# H-BRIDGE.net
KiCad netlist of a schematic drawn in Altium Designer
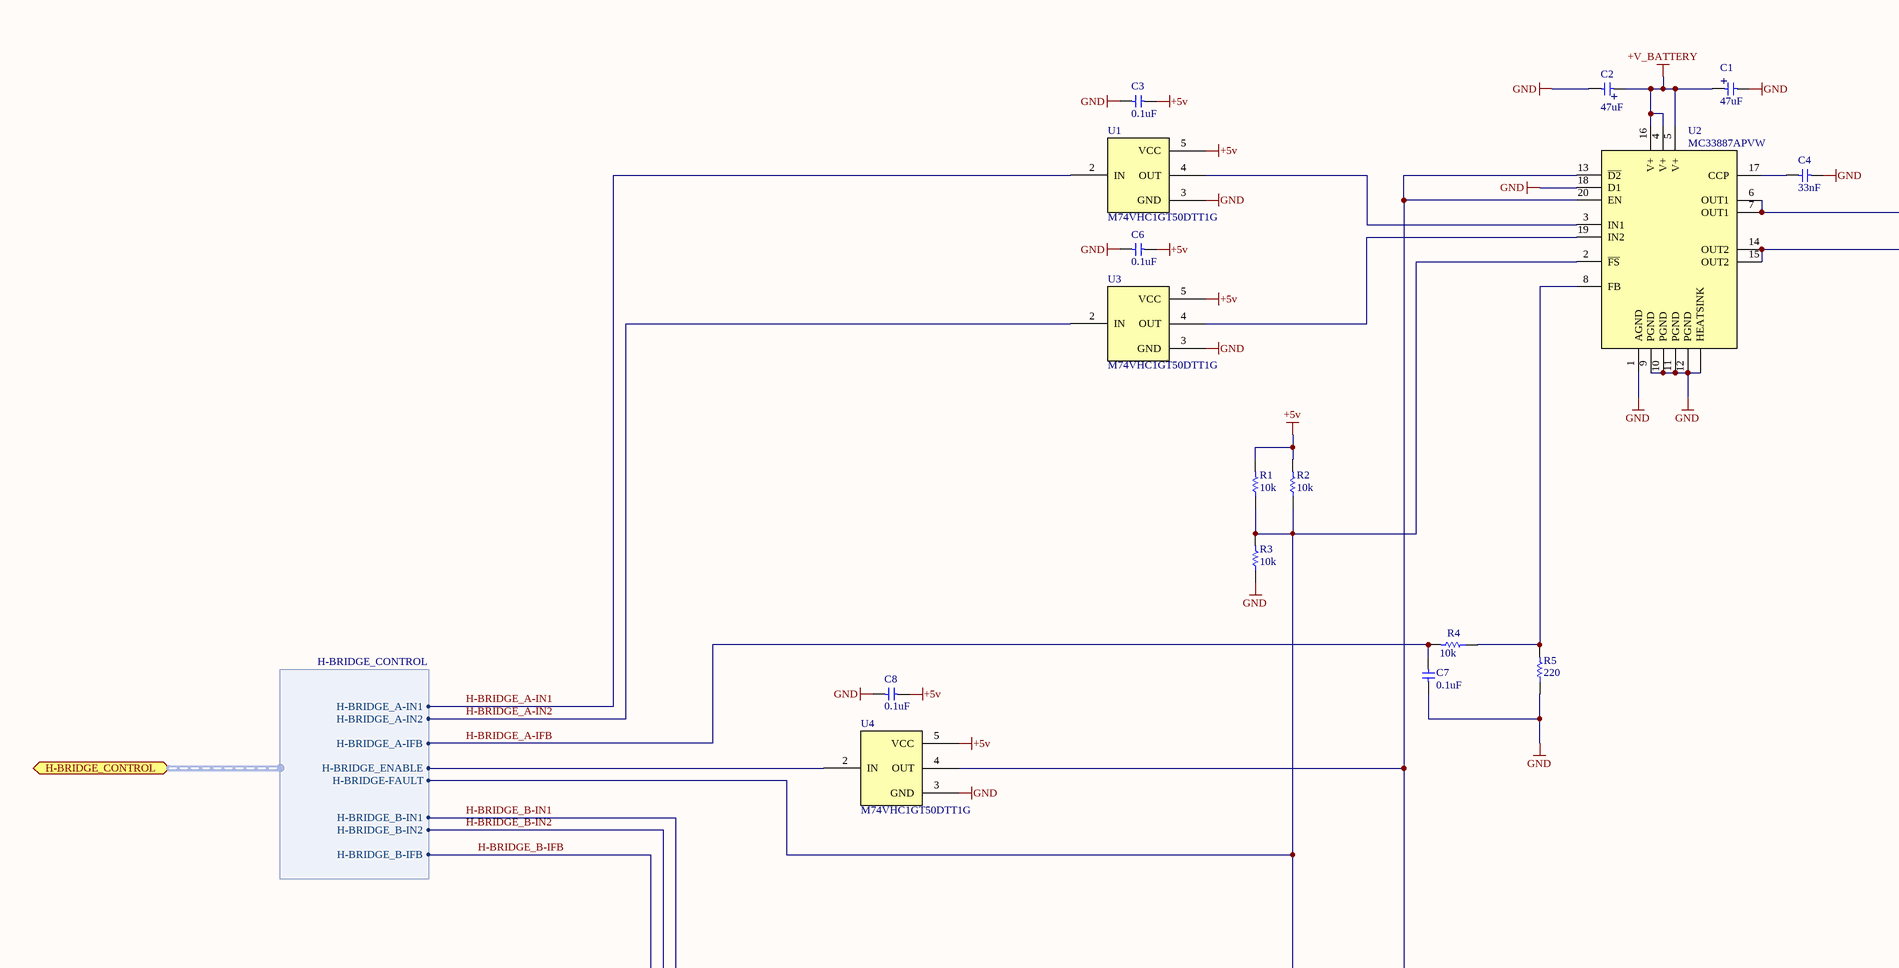
[diagram p0: H-BRIDGE.SchDoc, top left]
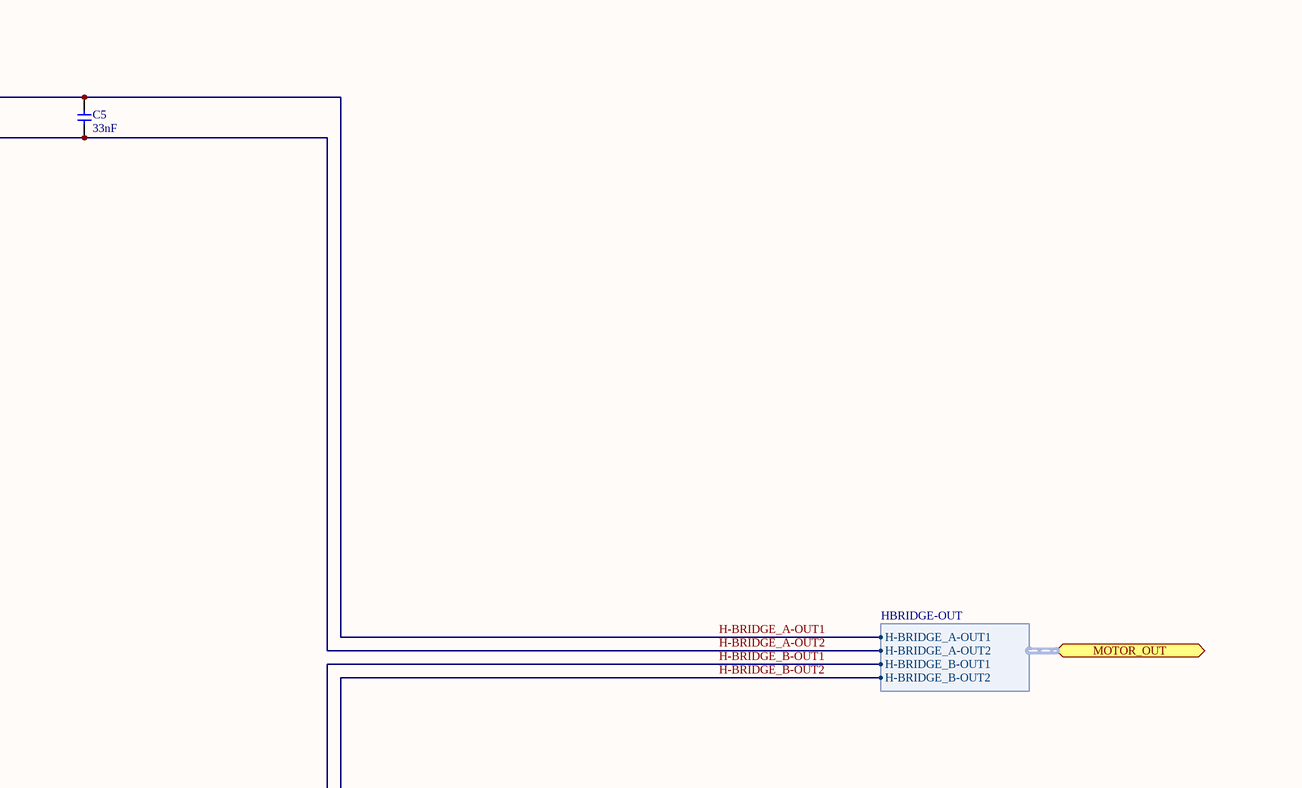
[diagram p1: H-BRIDGE.SchDoc, top right]
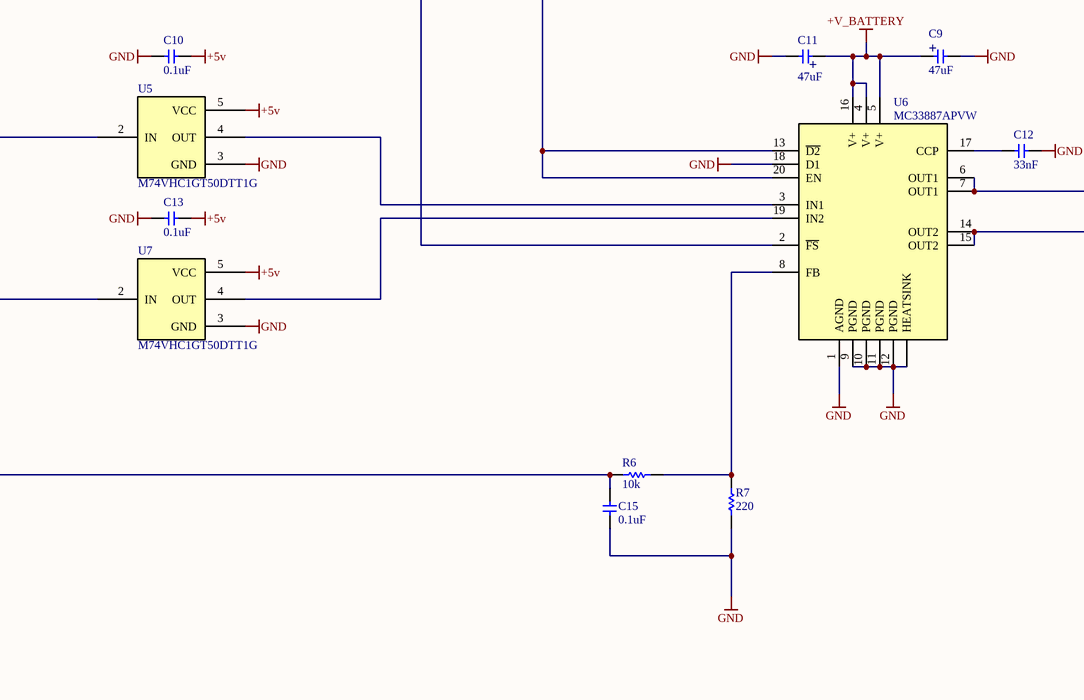
[diagram p2: H-BRIDGE.SchDoc, bottom left]
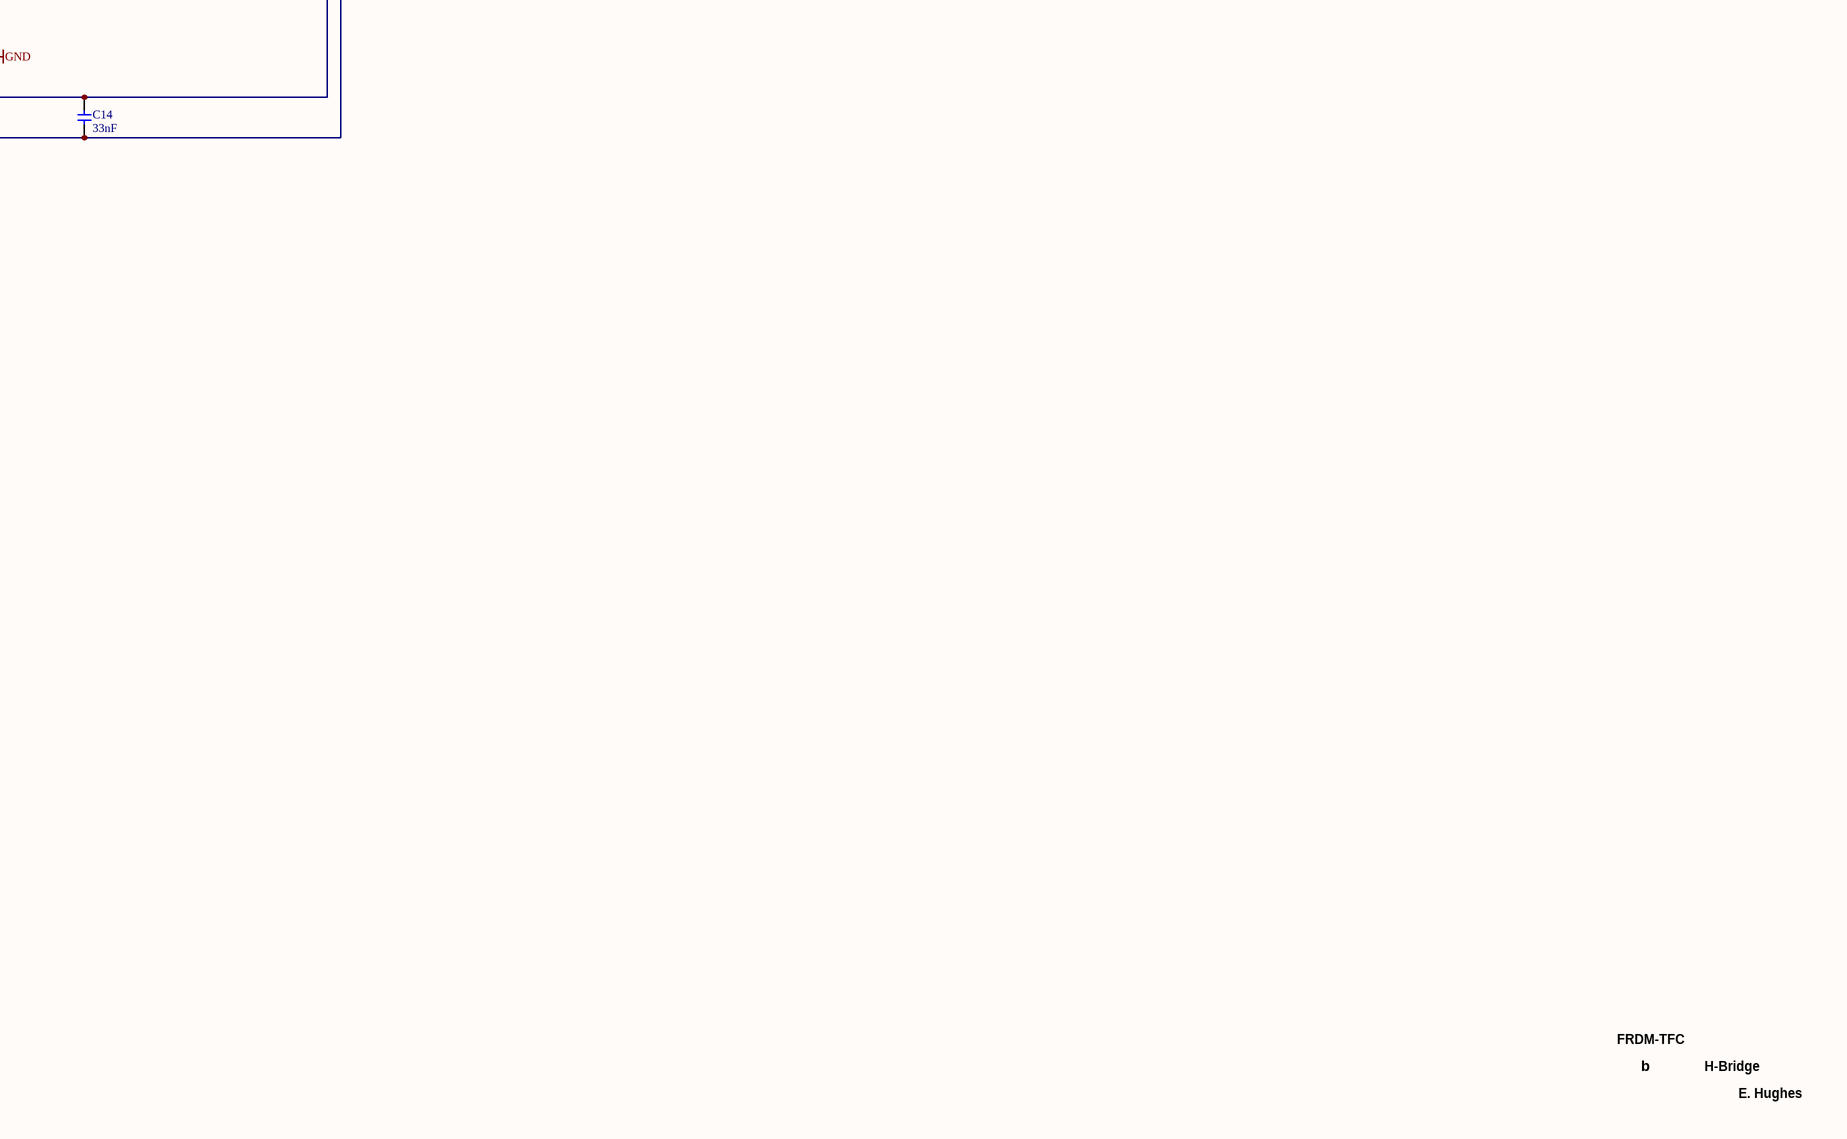
[diagram p3: H-BRIDGE.SchDoc, bottom right]

(export (version "E")
  (design (tool "Eeschema 10.0.6"))
  (components
    (comp (ref "C1")
      (value "47uF")
      (footprint "PANASONIC_D")
      (description "CAP ELECT 47UF 25V VS SMD")
      (fields
        (field (name "MANUFACTURER") "Panasonic - ECG")
        (field (name "MANUFACTURER PART NUMBER") "EEE-1EA470WP")
      )
      (libsource (lib "eCapacitors") (part "EEE-1EA470WP"))
    )
    (comp (ref "C2")
      (value "47uF")
      (footprint "PANASONIC_D")
      (description "CAP ELECT 47UF 25V VS SMD")
      (fields
        (field (name "MANUFACTURER") "Panasonic - ECG")
        (field (name "MANUFACTURER PART NUMBER") "EEE-1EA470WP")
      )
      (libsource (lib "eCapacitors") (part "EEE-1EA470WP"))
    )
    (comp (ref "C3")
      (value "0.1uF")
      (footprint "C0603")
      (description "CAP CER .1UF 50V 10% X7R 0603")
      (fields
        (field (name "MANUFACTURER") "Murata Electronics North America")
        (field (name "MANUFACTURER PART NUMBER") "GRM188R71H104KA93D")
      )
      (libsource (lib "eCapacitors") (part "GRM188R71H104KA93D"))
    )
    (comp (ref "C4")
      (value "33nF")
      (footprint "C0603")
      (description "CAP CER 0.033UF 50V 10% X7R 0603")
      (fields
        (field (name "MANUFACTURER") "Murata Electronics North America")
        (field (name "MANUFACTURER PART NUMBER") "GRM188R71H333KA61D")
      )
      (libsource (lib "eCapacitors") (part "GRM188R71H333KA61D"))
    )
    (comp (ref "C5")
      (value "33nF")
      (footprint "C0603")
      (description "CAP CER 0.033UF 50V 10% X7R 0603")
      (fields
        (field (name "MANUFACTURER") "Murata Electronics North America")
        (field (name "MANUFACTURER PART NUMBER") "GRM188R71H333KA61D")
      )
      (libsource (lib "eCapacitors") (part "GRM188R71H333KA61D"))
    )
    (comp (ref "C6")
      (value "0.1uF")
      (footprint "C0603")
      (description "CAP CER .1UF 50V 10% X7R 0603")
      (fields
        (field (name "MANUFACTURER") "Murata Electronics North America")
        (field (name "MANUFACTURER PART NUMBER") "GRM188R71H104KA93D")
      )
      (libsource (lib "eCapacitors") (part "GRM188R71H104KA93D"))
    )
    (comp (ref "C7")
      (value "0.1uF")
      (footprint "C0603")
      (description "CAP CER .1UF 50V 10% X7R 0603")
      (fields
        (field (name "MANUFACTURER") "Murata Electronics North America")
        (field (name "MANUFACTURER PART NUMBER") "GRM188R71H104KA93D")
      )
      (libsource (lib "eCapacitors") (part "GRM188R71H104KA93D"))
    )
    (comp (ref "C8")
      (value "0.1uF")
      (footprint "C0603")
      (description "CAP CER .1UF 50V 10% X7R 0603")
      (fields
        (field (name "MANUFACTURER") "Murata Electronics North America")
        (field (name "MANUFACTURER PART NUMBER") "GRM188R71H104KA93D")
      )
      (libsource (lib "eCapacitors") (part "GRM188R71H104KA93D"))
    )
    (comp (ref "C9")
      (value "47uF")
      (footprint "PANASONIC_D")
      (description "CAP ELECT 47UF 25V VS SMD")
      (fields
        (field (name "MANUFACTURER") "Panasonic - ECG")
        (field (name "MANUFACTURER PART NUMBER") "EEE-1EA470WP")
      )
      (libsource (lib "eCapacitors") (part "EEE-1EA470WP"))
    )
    (comp (ref "C10")
      (value "0.1uF")
      (footprint "C0603")
      (description "CAP CER .1UF 50V 10% X7R 0603")
      (fields
        (field (name "MANUFACTURER") "Murata Electronics North America")
        (field (name "MANUFACTURER PART NUMBER") "GRM188R71H104KA93D")
      )
      (libsource (lib "eCapacitors") (part "GRM188R71H104KA93D"))
    )
    (comp (ref "C11")
      (value "47uF")
      (footprint "PANASONIC_D")
      (description "CAP ELECT 47UF 25V VS SMD")
      (fields
        (field (name "MANUFACTURER") "Panasonic - ECG")
        (field (name "MANUFACTURER PART NUMBER") "EEE-1EA470WP")
      )
      (libsource (lib "eCapacitors") (part "EEE-1EA470WP"))
    )
    (comp (ref "C12")
      (value "33nF")
      (footprint "C0603")
      (description "CAP CER 0.033UF 50V 10% X7R 0603")
      (fields
        (field (name "MANUFACTURER") "Murata Electronics North America")
        (field (name "MANUFACTURER PART NUMBER") "GRM188R71H333KA61D")
      )
      (libsource (lib "eCapacitors") (part "GRM188R71H333KA61D"))
    )
    (comp (ref "C13")
      (value "0.1uF")
      (footprint "C0603")
      (description "CAP CER .1UF 50V 10% X7R 0603")
      (fields
        (field (name "MANUFACTURER") "Murata Electronics North America")
        (field (name "MANUFACTURER PART NUMBER") "GRM188R71H104KA93D")
      )
      (libsource (lib "eCapacitors") (part "GRM188R71H104KA93D"))
    )
    (comp (ref "C14")
      (value "33nF")
      (footprint "C0603")
      (description "CAP CER 0.033UF 50V 10% X7R 0603")
      (fields
        (field (name "MANUFACTURER") "Murata Electronics North America")
        (field (name "MANUFACTURER PART NUMBER") "GRM188R71H333KA61D")
      )
      (libsource (lib "eCapacitors") (part "GRM188R71H333KA61D"))
    )
    (comp (ref "C15")
      (value "0.1uF")
      (footprint "C0603")
      (description "CAP CER .1UF 50V 10% X7R 0603")
      (fields
        (field (name "MANUFACTURER") "Murata Electronics North America")
        (field (name "MANUFACTURER PART NUMBER") "GRM188R71H104KA93D")
      )
      (libsource (lib "eCapacitors") (part "GRM188R71H104KA93D"))
    )
    (comp (ref "R1")
      (value "10k")
      (footprint "R0603")
      (description "RES 10.0K OHM 1/10W 1% 0603 SMD")
      (fields
        (field (name "MANUFACTURER") "Panasonic - ECG")
        (field (name "TOLERANCE") "±1%")
        (field (name "SOURCE") "Digikey")
      )
      (libsource (lib "eRCL") (part "ERJ-3EKF1002V"))
    )
    (comp (ref "R2")
      (value "10k")
      (footprint "R0603")
      (description "RES 10.0K OHM 1/10W 1% 0603 SMD")
      (fields
        (field (name "MANUFACTURER") "Panasonic - ECG")
        (field (name "TOLERANCE") "±1%")
        (field (name "SOURCE") "Digikey")
      )
      (libsource (lib "eRCL") (part "ERJ-3EKF1002V"))
    )
    (comp (ref "R3")
      (value "10k")
      (footprint "R0603")
      (description "RES 10.0K OHM 1/10W 1% 0603 SMD")
      (fields
        (field (name "MANUFACTURER") "Panasonic - ECG")
        (field (name "TOLERANCE") "±1%")
        (field (name "SOURCE") "Digikey")
      )
      (libsource (lib "eRCL") (part "ERJ-3EKF1002V"))
    )
    (comp (ref "R4")
      (value "10k")
      (footprint "R0603")
      (description "RES 10.0K OHM 1/10W 1% 0603 SMD")
      (fields
        (field (name "MANUFACTURER") "Panasonic - ECG")
        (field (name "TOLERANCE") "±1%")
        (field (name "SOURCE") "Digikey")
      )
      (libsource (lib "eRCL") (part "ERJ-3EKF1002V"))
    )
    (comp (ref "R5")
      (value "220")
      (footprint "R0603")
      (description "RES 220 OHM 1/10W 1% 0603 SMD")
      (fields
        (field (name "MANUFACTURER") "Panasonic - ECG")
        (field (name "MANUFACTURER PART NUMBER") "ERJ-3EKF2200V")
      )
      (libsource (lib "eResistors") (part "ERJ-3EKF2200V"))
    )
    (comp (ref "R6")
      (value "10k")
      (footprint "R0603")
      (description "RES 10.0K OHM 1/10W 1% 0603 SMD")
      (fields
        (field (name "MANUFACTURER") "Panasonic - ECG")
        (field (name "TOLERANCE") "±1%")
        (field (name "SOURCE") "Digikey")
      )
      (libsource (lib "eRCL") (part "ERJ-3EKF1002V"))
    )
    (comp (ref "R7")
      (value "220")
      (footprint "R0603")
      (description "RES 220 OHM 1/10W 1% 0603 SMD")
      (fields
        (field (name "MANUFACTURER") "Panasonic - ECG")
        (field (name "MANUFACTURER PART NUMBER") "ERJ-3EKF2200V")
      )
      (libsource (lib "eResistors") (part "ERJ-3EKF2200V"))
    )
    (comp (ref "U1")
      (value "M74VHC1GT50DTT1G")
      (footprint "SOT95P245X145-5L")
      (description "IC BUFF CMOS LVL/SFTR N-I SOT235")
      (fields (field (name "MANUFACTURER") "ON Semiconductor"))
      (libsource (lib "eIC") (part "M74VHC1GT50DTT1G"))
    )
    (comp (ref "U2")
      (value "MC33887APVW")
      (footprint "FREESCALE HSOP-20")
      (description "Motor / Motion / Ignition Controllers & Drivers H-BRIDGE W/LD CURNT FDBK")
      (fields (field (name "MANUFACTURER") "Freescale Semiconductor"))
      (libsource (lib "eIC") (part "MC33887APVW"))
    )
    (comp (ref "U3")
      (value "M74VHC1GT50DTT1G")
      (footprint "SOT95P245X145-5L")
      (description "IC BUFF CMOS LVL/SFTR N-I SOT235")
      (fields (field (name "MANUFACTURER") "ON Semiconductor"))
      (libsource (lib "eIC") (part "M74VHC1GT50DTT1G"))
    )
    (comp (ref "U4")
      (value "M74VHC1GT50DTT1G")
      (footprint "SOT95P245X145-5L")
      (description "IC BUFF CMOS LVL/SFTR N-I SOT235")
      (fields (field (name "MANUFACTURER") "ON Semiconductor"))
      (libsource (lib "eIC") (part "M74VHC1GT50DTT1G"))
    )
    (comp (ref "U5")
      (value "M74VHC1GT50DTT1G")
      (footprint "SOT95P245X145-5L")
      (description "IC BUFF CMOS LVL/SFTR N-I SOT235")
      (fields (field (name "MANUFACTURER") "ON Semiconductor"))
      (libsource (lib "eIC") (part "M74VHC1GT50DTT1G"))
    )
    (comp (ref "U6")
      (value "MC33887APVW")
      (footprint "FREESCALE HSOP-20")
      (description "Motor / Motion / Ignition Controllers & Drivers H-BRIDGE W/LD CURNT FDBK")
      (fields (field (name "MANUFACTURER") "Freescale Semiconductor"))
      (libsource (lib "eIC") (part "MC33887APVW"))
    )
    (comp (ref "U7")
      (value "M74VHC1GT50DTT1G")
      (footprint "SOT95P245X145-5L")
      (description "IC BUFF CMOS LVL/SFTR N-I SOT235")
      (fields (field (name "MANUFACTURER") "ON Semiconductor"))
      (libsource (lib "eIC") (part "M74VHC1GT50DTT1G"))
    )
  )
  (nets
    (net (code "3") (name "+5v") (class "Default")
      (node (ref "C10") (pin "2") (pinfunction "2_2") (pintype "passive"))
      (node (ref "C13") (pin "2") (pinfunction "2_2") (pintype "passive"))
      (node (ref "C3") (pin "2") (pinfunction "2_2") (pintype "passive"))
      (node (ref "C6") (pin "2") (pinfunction "2_2") (pintype "passive"))
      (node (ref "C8") (pin "2") (pinfunction "2_2") (pintype "passive"))
      (node (ref "R1") (pin "2") (pinfunction "2_2") (pintype "passive"))
      (node (ref "R2") (pin "2") (pinfunction "2_2") (pintype "passive"))
      (node (ref "U1") (pin "5") (pinfunction "VCC_5") (pintype "passive"))
      (node (ref "U3") (pin "5") (pinfunction "VCC_5") (pintype "passive"))
      (node (ref "U4") (pin "5") (pinfunction "VCC_5") (pintype "passive"))
      (node (ref "U5") (pin "5") (pinfunction "VCC_5") (pintype "passive"))
      (node (ref "U7") (pin "5") (pinfunction "VCC_5") (pintype "passive"))
    )
    (net (code "4") (name "+V_BATTERY") (class "Default")
      (node (ref "C1") (pin "1") (pinfunction "1_1") (pintype "passive"))
      (node (ref "C11") (pin "1") (pinfunction "1_1") (pintype "passive"))
      (node (ref "C2") (pin "1") (pinfunction "1_1") (pintype "passive"))
      (node (ref "C9") (pin "1") (pinfunction "1_1") (pintype "passive"))
      (node (ref "U2") (pin "16") (pinfunction "V+_16") (pintype "passive"))
      (node (ref "U2") (pin "4") (pinfunction "V+_4") (pintype "passive"))
      (node (ref "U2") (pin "5") (pinfunction "V+_5") (pintype "passive"))
      (node (ref "U6") (pin "16") (pinfunction "V+_16") (pintype "passive"))
      (node (ref "U6") (pin "4") (pinfunction "V+_4") (pintype "passive"))
      (node (ref "U6") (pin "5") (pinfunction "V+_5") (pintype "passive"))
    )
    (net (code "5") (name "/H-BRIDGE-FAULT") (class "Default")
      (node (ref "R1") (pin "1") (pinfunction "1_1") (pintype "passive"))
      (node (ref "R2") (pin "1") (pinfunction "1_1") (pintype "passive"))
      (node (ref "R3") (pin "2") (pinfunction "2_2") (pintype "passive"))
      (node (ref "U2") (pin "2") (pinfunction "~{FS}_2") (pintype "passive"))
      (node (ref "U6") (pin "2") (pinfunction "~{FS}_2") (pintype "passive"))
    )
    (net (code "6") (name "/H-BRIDGE_A-IFB") (class "Default")
      (node (ref "C7") (pin "1") (pinfunction "1_1") (pintype "passive"))
      (node (ref "R4") (pin "2") (pinfunction "2_2") (pintype "passive"))
    )
    (net (code "7") (name "/H-BRIDGE_A-IN1") (class "Default")
      (node (ref "U1") (pin "2") (pinfunction "IN_2") (pintype "passive"))
    )
    (net (code "8") (name "/H-BRIDGE_A-IN2") (class "Default")
      (node (ref "U3") (pin "2") (pinfunction "IN_2") (pintype "passive"))
    )
    (net (code "9") (name "/H-BRIDGE_A-OUT1") (class "Default")
      (node (ref "C5") (pin "2") (pinfunction "2_2") (pintype "passive"))
      (node (ref "U2") (pin "6") (pinfunction "OUT1_6") (pintype "passive"))
      (node (ref "U2") (pin "7") (pinfunction "OUT1_7") (pintype "passive"))
    )
    (net (code "10") (name "/H-BRIDGE_A-OUT2") (class "Default")
      (node (ref "C5") (pin "1") (pinfunction "1_1") (pintype "passive"))
      (node (ref "U2") (pin "14") (pinfunction "OUT2_14") (pintype "passive"))
      (node (ref "U2") (pin "15") (pinfunction "OUT2_15") (pintype "passive"))
    )
    (net (code "11") (name "/H-BRIDGE_B-IFB") (class "Default")
      (node (ref "C15") (pin "1") (pinfunction "1_1") (pintype "passive"))
      (node (ref "R6") (pin "2") (pinfunction "2_2") (pintype "passive"))
    )
    (net (code "12") (name "/H-BRIDGE_B-IN1") (class "Default")
      (node (ref "U5") (pin "2") (pinfunction "IN_2") (pintype "passive"))
    )
    (net (code "13") (name "/H-BRIDGE_B-IN2") (class "Default")
      (node (ref "U7") (pin "2") (pinfunction "IN_2") (pintype "passive"))
    )
    (net (code "14") (name "/H-BRIDGE_B-OUT1") (class "Default")
      (node (ref "C14") (pin "2") (pinfunction "2_2") (pintype "passive"))
      (node (ref "U6") (pin "6") (pinfunction "OUT1_6") (pintype "passive"))
      (node (ref "U6") (pin "7") (pinfunction "OUT1_7") (pintype "passive"))
    )
    (net (code "15") (name "/H-BRIDGE_B-OUT2") (class "Default")
      (node (ref "C14") (pin "1") (pinfunction "1_1") (pintype "passive"))
      (node (ref "U6") (pin "14") (pinfunction "OUT2_14") (pintype "passive"))
      (node (ref "U6") (pin "15") (pinfunction "OUT2_15") (pintype "passive"))
    )
    (net (code "16") (name "/H-BRIDGE_ENABLE") (class "Default")
      (node (ref "U4") (pin "2") (pinfunction "IN_2") (pintype "passive"))
    )
    (net (code "19") (name "GND") (class "Default")
      (node (ref "C1") (pin "2") (pinfunction "2_2") (pintype "passive"))
      (node (ref "C10") (pin "1") (pinfunction "1_1") (pintype "passive"))
      (node (ref "C11") (pin "2") (pinfunction "2_2") (pintype "passive"))
      (node (ref "C12") (pin "2") (pinfunction "2_2") (pintype "passive"))
      (node (ref "C13") (pin "1") (pinfunction "1_1") (pintype "passive"))
      (node (ref "C15") (pin "2") (pinfunction "2_2") (pintype "passive"))
      (node (ref "C2") (pin "2") (pinfunction "2_2") (pintype "passive"))
      (node (ref "C3") (pin "1") (pinfunction "1_1") (pintype "passive"))
      (node (ref "C4") (pin "2") (pinfunction "2_2") (pintype "passive"))
      (node (ref "C6") (pin "1") (pinfunction "1_1") (pintype "passive"))
      (node (ref "C7") (pin "2") (pinfunction "2_2") (pintype "passive"))
      (node (ref "C8") (pin "1") (pinfunction "1_1") (pintype "passive"))
      (node (ref "C9") (pin "2") (pinfunction "2_2") (pintype "passive"))
      (node (ref "R3") (pin "1") (pinfunction "1_1") (pintype "passive"))
      (node (ref "R5") (pin "1") (pinfunction "1_1") (pintype "passive"))
      (node (ref "R7") (pin "1") (pinfunction "1_1") (pintype "passive"))
      (node (ref "U1") (pin "3") (pinfunction "GND_3") (pintype "passive"))
      (node (ref "U2") (pin "1") (pinfunction "AGND_1") (pintype "passive"))
      (node (ref "U2") (pin "10") (pinfunction "PGND_10") (pintype "passive"))
      (node (ref "U2") (pin "11") (pinfunction "PGND_11") (pintype "passive"))
      (node (ref "U2") (pin "12") (pinfunction "PGND_12") (pintype "passive"))
      (node (ref "U2") (pin "18") (pinfunction "D1_18") (pintype "passive"))
      (node (ref "U2") (pin "9") (pinfunction "PGND_9") (pintype "passive"))
      (node (ref "U2") (pin "HEATSINK") (pinfunction "HEATSINK_HEATSINK") (pintype "passive"))
      (node (ref "U3") (pin "3") (pinfunction "GND_3") (pintype "passive"))
      (node (ref "U4") (pin "3") (pinfunction "GND_3") (pintype "passive"))
      (node (ref "U5") (pin "3") (pinfunction "GND_3") (pintype "passive"))
      (node (ref "U6") (pin "1") (pinfunction "AGND_1") (pintype "passive"))
      (node (ref "U6") (pin "10") (pinfunction "PGND_10") (pintype "passive"))
      (node (ref "U6") (pin "11") (pinfunction "PGND_11") (pintype "passive"))
      (node (ref "U6") (pin "12") (pinfunction "PGND_12") (pintype "passive"))
      (node (ref "U6") (pin "18") (pinfunction "D1_18") (pintype "passive"))
      (node (ref "U6") (pin "9") (pinfunction "PGND_9") (pintype "passive"))
      (node (ref "U6") (pin "HEATSINK") (pinfunction "HEATSINK_HEATSINK") (pintype "passive"))
      (node (ref "U7") (pin "3") (pinfunction "GND_3") (pintype "passive"))
    )
    (net (code "20") (name "Net-(U1-OUT)") (class "Default")
      (node (ref "U1") (pin "4") (pinfunction "OUT_4") (pintype "passive"))
      (node (ref "U2") (pin "3") (pinfunction "IN1_3") (pintype "passive"))
    )
    (net (code "21") (name "Net-(U2-CCP)") (class "Default")
      (node (ref "C4") (pin "1") (pinfunction "1_1") (pintype "passive"))
      (node (ref "U2") (pin "17") (pinfunction "CCP_17") (pintype "passive"))
    )
    (net (code "22") (name "Net-(U2-EN)") (class "Default")
      (node (ref "U2") (pin "13") (pinfunction "~{D2}_13") (pintype "passive"))
      (node (ref "U2") (pin "20") (pinfunction "EN_20") (pintype "passive"))
      (node (ref "U4") (pin "4") (pinfunction "OUT_4") (pintype "passive"))
      (node (ref "U6") (pin "13") (pinfunction "~{D2}_13") (pintype "passive"))
      (node (ref "U6") (pin "20") (pinfunction "EN_20") (pintype "passive"))
    )
    (net (code "23") (name "Net-(U2-FB)") (class "Default")
      (node (ref "R4") (pin "1") (pinfunction "1_1") (pintype "passive"))
      (node (ref "R5") (pin "2") (pinfunction "2_2") (pintype "passive"))
      (node (ref "U2") (pin "8") (pinfunction "FB_8") (pintype "passive"))
    )
    (net (code "24") (name "Net-(U2-IN2)") (class "Default")
      (node (ref "U2") (pin "19") (pinfunction "IN2_19") (pintype "passive"))
      (node (ref "U3") (pin "4") (pinfunction "OUT_4") (pintype "passive"))
    )
    (net (code "25") (name "Net-(U5-OUT)") (class "Default")
      (node (ref "U5") (pin "4") (pinfunction "OUT_4") (pintype "passive"))
      (node (ref "U6") (pin "3") (pinfunction "IN1_3") (pintype "passive"))
    )
    (net (code "26") (name "Net-(U6-CCP)") (class "Default")
      (node (ref "C12") (pin "1") (pinfunction "1_1") (pintype "passive"))
      (node (ref "U6") (pin "17") (pinfunction "CCP_17") (pintype "passive"))
    )
    (net (code "27") (name "Net-(U6-FB)") (class "Default")
      (node (ref "R6") (pin "1") (pinfunction "1_1") (pintype "passive"))
      (node (ref "R7") (pin "2") (pinfunction "2_2") (pintype "passive"))
      (node (ref "U6") (pin "8") (pinfunction "FB_8") (pintype "passive"))
    )
    (net (code "28") (name "Net-(U6-IN2)") (class "Default")
      (node (ref "U6") (pin "19") (pinfunction "IN2_19") (pintype "passive"))
      (node (ref "U7") (pin "4") (pinfunction "OUT_4") (pintype "passive"))
    )
  )
)
